# Controller_-_ESP32_Wroom_-_Rev_B.net
KiCad netlist of a schematic drawn in EAGLE
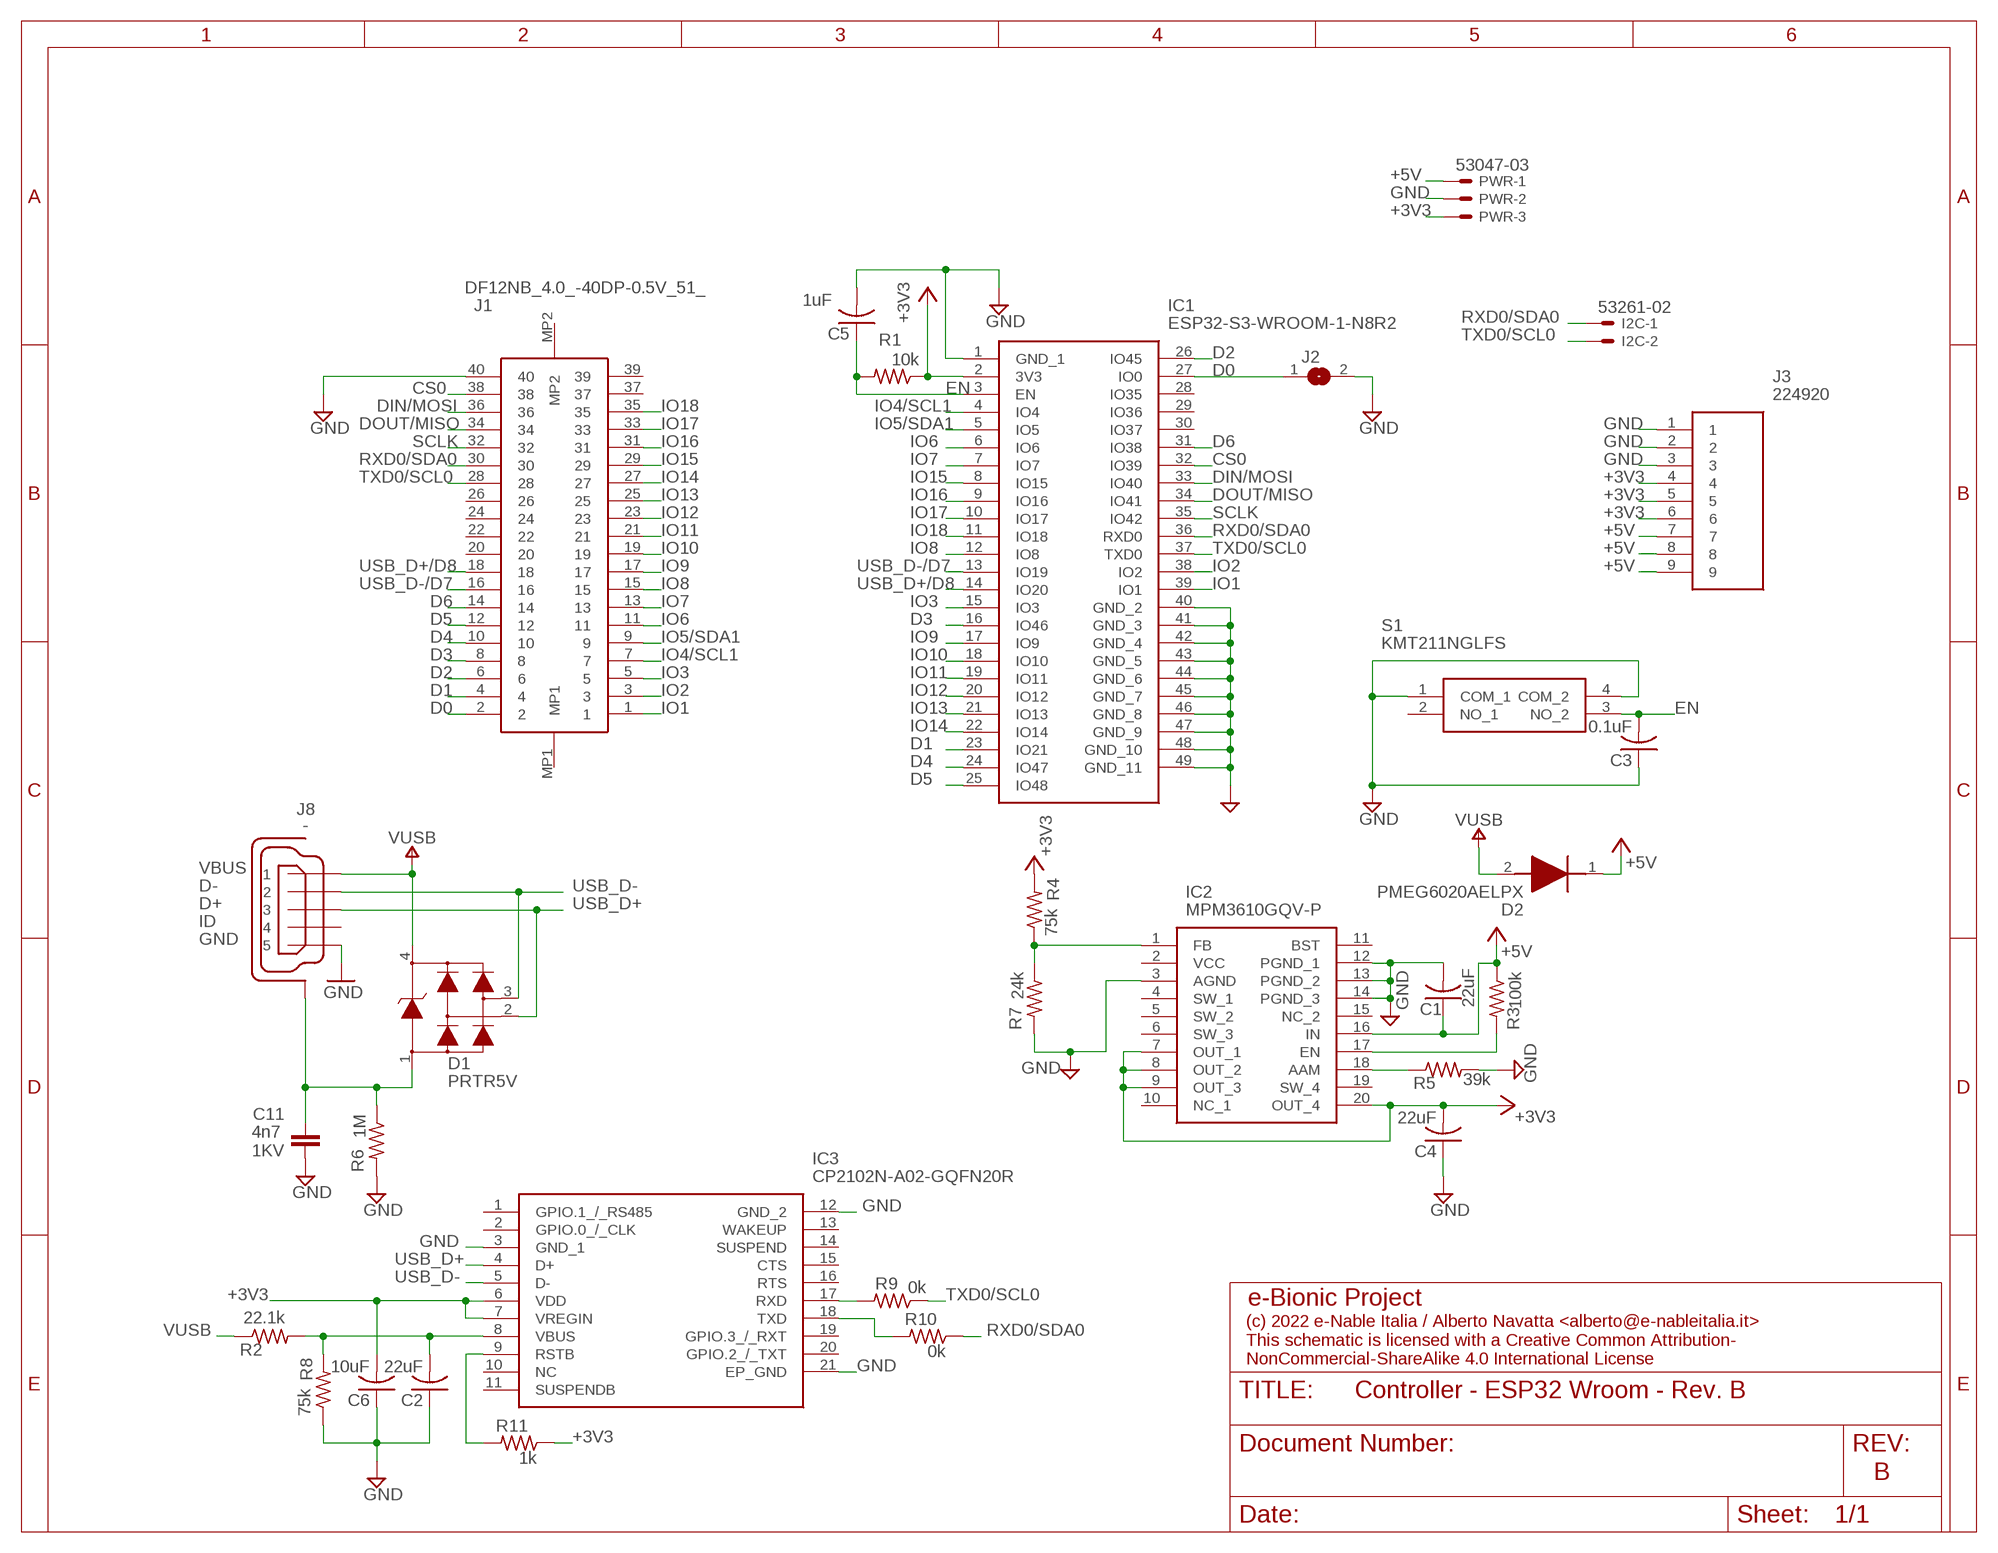
[diagram p0: schematic, sheet 1]

(export (version "E")
  (design (tool "Eeschema 10.0.6"))
  (components
    (comp (ref "C1")
      (value "22uF")
      (footprint "eagle-import:C0603")
      (libsource (lib "eagle-import") (part "C-USC0603"))
    )
    (comp (ref "C2")
      (value "22uF")
      (footprint "eagle-import:C0402")
      (libsource (lib "eagle-import") (part "C-USC0402"))
    )
    (comp (ref "C3")
      (value "0.1uF")
      (footprint "eagle-import:C0402")
      (libsource (lib "eagle-import") (part "C-USC0402"))
    )
    (comp (ref "C4")
      (value "22uF")
      (footprint "eagle-import:C0603")
      (libsource (lib "eagle-import") (part "C-USC0603"))
    )
    (comp (ref "C5")
      (value "1uF")
      (footprint "eagle-import:C0402")
      (libsource (lib "eagle-import") (part "C-USC0402"))
    )
    (comp (ref "C6")
      (value "10uF")
      (footprint "eagle-import:C0402")
      (libsource (lib "eagle-import") (part "C-USC0402"))
    )
    (comp (ref "C11")
      (value "4n7")
      (footprint "eagle-import:0805-R2013X50N")
      (fields (field (name "MANUFACTURER") "Kemet") (field (name "VOLTAGE") "1KV"))
      (libsource (lib "eagle-import") (part "C-08054.7NF"))
    )
    (comp (ref "D1")
      (value "PRTR5V")
      (footprint "eagle-import:SOT190P230X110-4N")
      (fields (field (name "MANUFACTURER") "NXP"))
      (libsource (lib "eagle-import") (part "PRTR5V0U2X,215"))
    )
    (comp (ref "D2")
      (value "PMEG6020AELPX")
      (footprint "eagle-import:SODFL4725X110N")
      (fields (field (name "MOUSER_PART_NUMBER") "771-PMEG6020AELPX"))
      (libsource (lib "eagle-import") (part "PMEG6020AELPX"))
    )
    (comp (ref "I2C")
      (value "53261-02")
      (footprint "eagle-import:53261-02")
      (fields (field (name "MF") "MOLEX"))
      (libsource (lib "eagle-import") (part "53?-02261"))
    )
    (comp (ref "IC1")
      (value "ESP32-S3-WROOM-1-N8R2")
      (footprint "eagle-import:ESP32S3WROOM1N8R2")
      (fields (field (name "MOUSER_PART_NUMBER") "356-ESP32-S3WRM1N8R2"))
      (libsource (lib "eagle-import") (part "ESP32-S3-WROOM-1-N8R2"))
    )
    (comp (ref "IC2")
      (value "MPM3610GQV-P")
      (footprint "eagle-import:MPM3610GQVP")
      (fields (field (name "MOUSER_PART_NUMBER") "946-MPM3610GQV-P"))
      (libsource (lib "eagle-import") (part "MPM3610GQV-P"))
    )
    (comp (ref "IC3")
      (value "CP2102N-A02-GQFN20R")
      (footprint "eagle-import:CP2102NA02GQFN20")
      (fields (field (name "MOUSER_PART_NUMBER") "634-CP2102NA02QFN20R"))
      (libsource (lib "eagle-import") (part "CP2102N-A02-GQFN20R"))
    )
    (comp (ref "J1")
      (value "DF12NB_4.0_-40DP-0.5V_51_")
      (footprint "eagle-import:DF12NB4040DP05V51")
      (fields
        (field (name "MANUFACTURER_PART_NUMBER") "DF12NB(4.0)-40DP-0.5V(51)")
        (field (name "MOUSER_PART_NUMBER") "798-DF12NB4040DP0551")
      )
      (libsource (lib "eagle-import") (part "DF12NB_4.0_-40DP-0.5V_51_"))
    )
    (comp (ref "J2") (value "SJ") (footprint "eagle-import:SJ") (libsource (lib "eagle-import") (part "SJ")))
    (comp (ref "J3")
      (value "224920")
      (footprint "eagle-import:224920")
      (fields (field (name "MOUSER_PART_NUMBER") "305-224920"))
      (libsource (lib "eagle-import") (part "224920"))
    )
    (comp (ref "J8")
      (value "-")
      (footprint "eagle-import:ZX62-AB-5PA")
      (fields (field (name "MANUFACTURER") "Hirose"))
      (libsource (lib "eagle-import") (part "USB-MICRO"))
    )
    (comp (ref "PWR")
      (value "53047-03")
      (footprint "eagle-import:53047-03")
      (fields (field (name "MF") "MOLEX") (field (name "MPN") "530470310"))
      (libsource (lib "eagle-import") (part "53?-03047"))
    )
    (comp (ref "R1")
      (value "10k")
      (footprint "eagle-import:R0402")
      (libsource (lib "eagle-import") (part "R-US_R0402"))
    )
    (comp (ref "R2")
      (value "22.1k")
      (footprint "eagle-import:R0402")
      (libsource (lib "eagle-import") (part "R-US_R0402"))
    )
    (comp (ref "R3")
      (value "100k")
      (footprint "eagle-import:R0402")
      (libsource (lib "eagle-import") (part "R-US_R0402"))
    )
    (comp (ref "R4")
      (value "75k")
      (footprint "eagle-import:R0402")
      (libsource (lib "eagle-import") (part "R-US_R0402"))
    )
    (comp (ref "R5")
      (value "39k")
      (footprint "eagle-import:R0402")
      (libsource (lib "eagle-import") (part "R-US_R0402"))
    )
    (comp (ref "R6")
      (value "1M")
      (footprint "eagle-import:R0402")
      (libsource (lib "eagle-import") (part "R-US_R0402"))
    )
    (comp (ref "R7")
      (value "24k")
      (footprint "eagle-import:R0402")
      (libsource (lib "eagle-import") (part "R-US_R0402"))
    )
    (comp (ref "R8")
      (value "75k")
      (footprint "eagle-import:R0402")
      (libsource (lib "eagle-import") (part "R-US_R0402"))
    )
    (comp (ref "R9")
      (value "0k")
      (footprint "eagle-import:R0402")
      (libsource (lib "eagle-import") (part "R-US_R0402"))
    )
    (comp (ref "R10")
      (value "0k")
      (footprint "eagle-import:R0402")
      (libsource (lib "eagle-import") (part "R-US_R0402"))
    )
    (comp (ref "R11")
      (value "1k")
      (footprint "eagle-import:R0402")
      (libsource (lib "eagle-import") (part "R-US_R0402"))
    )
    (comp (ref "S1")
      (value "KMT211NGLFS")
      (footprint "eagle-import:KMT211NGLFS")
      (fields (field (name "MOUSER_PART_NUMBER") "611-KMT211NGLFS"))
      (libsource (lib "eagle-import") (part "KMT211NGLFS"))
    )
  )
  (nets
    (net (code "1") (name "+3V3") (class "Default")
      (node (ref "C4") (pin "2") (pinfunction "2_2") (pintype "passive"))
      (node (ref "C6") (pin "2") (pinfunction "2_2") (pintype "passive"))
      (node (ref "IC1") (pin "2") (pinfunction "3V3_2") (pintype "bidirectional"))
      (node (ref "IC2") (pin "20") (pinfunction "OUT_4_20") (pintype "bidirectional"))
      (node (ref "IC2") (pin "7") (pinfunction "OUT_1_7") (pintype "bidirectional"))
      (node (ref "IC2") (pin "8") (pinfunction "OUT_2_8") (pintype "bidirectional"))
      (node (ref "IC2") (pin "9") (pinfunction "OUT_3_9") (pintype "bidirectional"))
      (node (ref "IC3") (pin "6") (pinfunction "VDD_6") (pintype "bidirectional"))
      (node (ref "IC3") (pin "7") (pinfunction "VREGIN_7") (pintype "bidirectional"))
      (node (ref "J3") (pin "4") (pinfunction "4_4") (pintype "bidirectional"))
      (node (ref "J3") (pin "5") (pinfunction "5_5") (pintype "bidirectional"))
      (node (ref "J3") (pin "6") (pinfunction "6_6") (pintype "bidirectional"))
      (node (ref "PWR") (pin "3") (pinfunction "S_3") (pintype "passive"))
      (node (ref "R1") (pin "1") (pinfunction "1_1") (pintype "passive"))
      (node (ref "R11") (pin "1") (pinfunction "1_1") (pintype "passive"))
      (node (ref "R4") (pin "2") (pinfunction "2_2") (pintype "passive"))
    )
    (net (code "2") (name "+5V") (class "Default")
      (node (ref "C1") (pin "1") (pinfunction "1_1") (pintype "passive"))
      (node (ref "D2") (pin "1") (pinfunction "K_1") (pintype "bidirectional"))
      (node (ref "IC2") (pin "16") (pinfunction "IN_16") (pintype "bidirectional"))
      (node (ref "J3") (pin "7") (pinfunction "7_7") (pintype "bidirectional"))
      (node (ref "J3") (pin "8") (pinfunction "8_8") (pintype "bidirectional"))
      (node (ref "J3") (pin "9") (pinfunction "9_9") (pintype "bidirectional"))
      (node (ref "PWR") (pin "1") (pinfunction "S_1") (pintype "passive"))
      (node (ref "R3") (pin "1") (pinfunction "1_1") (pintype "passive"))
    )
    (net (code "3") (name "/CS0") (class "Default")
      (node (ref "IC1") (pin "32") (pinfunction "IO39_32") (pintype "bidirectional"))
      (node (ref "J1") (pin "38") (pinfunction "38_38") (pintype "bidirectional"))
    )
    (net (code "4") (name "/D0") (class "Default")
      (node (ref "IC1") (pin "27") (pinfunction "IO0_27") (pintype "bidirectional"))
      (node (ref "J1") (pin "2") (pinfunction "2_2") (pintype "bidirectional"))
      (node (ref "J2") (pin "1") (pinfunction "1_1") (pintype "passive"))
    )
    (net (code "5") (name "/D1") (class "Default")
      (node (ref "IC1") (pin "23") (pinfunction "IO21_23") (pintype "bidirectional"))
      (node (ref "J1") (pin "4") (pinfunction "4_4") (pintype "bidirectional"))
    )
    (net (code "6") (name "/D2") (class "Default")
      (node (ref "IC1") (pin "26") (pinfunction "IO45_26") (pintype "bidirectional"))
      (node (ref "J1") (pin "6") (pinfunction "6_6") (pintype "bidirectional"))
    )
    (net (code "7") (name "/D3") (class "Default")
      (node (ref "IC1") (pin "16") (pinfunction "IO46_16") (pintype "bidirectional"))
      (node (ref "J1") (pin "8") (pinfunction "8_8") (pintype "bidirectional"))
    )
    (net (code "8") (name "/D4") (class "Default")
      (node (ref "IC1") (pin "24") (pinfunction "IO47_24") (pintype "bidirectional"))
      (node (ref "J1") (pin "10") (pinfunction "10_10") (pintype "bidirectional"))
    )
    (net (code "9") (name "/D5") (class "Default")
      (node (ref "IC1") (pin "25") (pinfunction "IO48_25") (pintype "bidirectional"))
      (node (ref "J1") (pin "12") (pinfunction "12_12") (pintype "bidirectional"))
    )
    (net (code "10") (name "/D6") (class "Default")
      (node (ref "IC1") (pin "31") (pinfunction "IO38_31") (pintype "bidirectional"))
      (node (ref "J1") (pin "14") (pinfunction "14_14") (pintype "bidirectional"))
    )
    (net (code "11") (name "/DIN{slash}MOSI") (class "Default")
      (node (ref "IC1") (pin "33") (pinfunction "IO40_33") (pintype "bidirectional"))
      (node (ref "J1") (pin "36") (pinfunction "36_36") (pintype "bidirectional"))
    )
    (net (code "12") (name "/DOUT{slash}MISO") (class "Default")
      (node (ref "IC1") (pin "34") (pinfunction "IO41_34") (pintype "bidirectional"))
      (node (ref "J1") (pin "34") (pinfunction "34_34") (pintype "bidirectional"))
    )
    (net (code "13") (name "/EN") (class "Default")
      (node (ref "C3") (pin "2") (pinfunction "2_2") (pintype "passive"))
      (node (ref "C5") (pin "1") (pinfunction "1_1") (pintype "passive"))
      (node (ref "IC1") (pin "3") (pinfunction "EN_3") (pintype "bidirectional"))
      (node (ref "R1") (pin "2") (pinfunction "2_2") (pintype "passive"))
      (node (ref "S1") (pin "3") (pinfunction "NO_2_3") (pintype "bidirectional"))
    )
    (net (code "14") (name "/IO1") (class "Default")
      (node (ref "IC1") (pin "39") (pinfunction "IO1_39") (pintype "bidirectional"))
      (node (ref "J1") (pin "1") (pinfunction "1_1") (pintype "bidirectional"))
    )
    (net (code "15") (name "/IO2") (class "Default")
      (node (ref "IC1") (pin "38") (pinfunction "IO2_38") (pintype "bidirectional"))
      (node (ref "J1") (pin "3") (pinfunction "3_3") (pintype "bidirectional"))
    )
    (net (code "16") (name "/IO3") (class "Default")
      (node (ref "IC1") (pin "15") (pinfunction "IO3_15") (pintype "bidirectional"))
      (node (ref "J1") (pin "5") (pinfunction "5_5") (pintype "bidirectional"))
    )
    (net (code "17") (name "/IO4{slash}SCL1") (class "Default")
      (node (ref "IC1") (pin "4") (pinfunction "IO4_4") (pintype "bidirectional"))
      (node (ref "J1") (pin "7") (pinfunction "7_7") (pintype "bidirectional"))
    )
    (net (code "18") (name "/IO5{slash}SDA1") (class "Default")
      (node (ref "IC1") (pin "5") (pinfunction "IO5_5") (pintype "bidirectional"))
      (node (ref "J1") (pin "9") (pinfunction "9_9") (pintype "bidirectional"))
    )
    (net (code "19") (name "/IO6") (class "Default")
      (node (ref "IC1") (pin "6") (pinfunction "IO6_6") (pintype "bidirectional"))
      (node (ref "J1") (pin "11") (pinfunction "11_11") (pintype "bidirectional"))
    )
    (net (code "20") (name "/IO7") (class "Default")
      (node (ref "IC1") (pin "7") (pinfunction "IO7_7") (pintype "bidirectional"))
      (node (ref "J1") (pin "13") (pinfunction "13_13") (pintype "bidirectional"))
    )
    (net (code "21") (name "/IO8") (class "Default")
      (node (ref "IC1") (pin "12") (pinfunction "IO8_12") (pintype "bidirectional"))
      (node (ref "J1") (pin "15") (pinfunction "15_15") (pintype "bidirectional"))
    )
    (net (code "22") (name "/IO9") (class "Default")
      (node (ref "IC1") (pin "17") (pinfunction "IO9_17") (pintype "bidirectional"))
      (node (ref "J1") (pin "17") (pinfunction "17_17") (pintype "bidirectional"))
    )
    (net (code "23") (name "/IO10") (class "Default")
      (node (ref "IC1") (pin "18") (pinfunction "IO10_18") (pintype "bidirectional"))
      (node (ref "J1") (pin "19") (pinfunction "19_19") (pintype "bidirectional"))
    )
    (net (code "24") (name "/IO11") (class "Default")
      (node (ref "IC1") (pin "19") (pinfunction "IO11_19") (pintype "bidirectional"))
      (node (ref "J1") (pin "21") (pinfunction "21_21") (pintype "bidirectional"))
    )
    (net (code "25") (name "/IO12") (class "Default")
      (node (ref "IC1") (pin "20") (pinfunction "IO12_20") (pintype "bidirectional"))
      (node (ref "J1") (pin "23") (pinfunction "23_23") (pintype "bidirectional"))
    )
    (net (code "26") (name "/IO13") (class "Default")
      (node (ref "IC1") (pin "21") (pinfunction "IO13_21") (pintype "bidirectional"))
      (node (ref "J1") (pin "25") (pinfunction "25_25") (pintype "bidirectional"))
    )
    (net (code "27") (name "/IO14") (class "Default")
      (node (ref "IC1") (pin "22") (pinfunction "IO14_22") (pintype "bidirectional"))
      (node (ref "J1") (pin "27") (pinfunction "27_27") (pintype "bidirectional"))
    )
    (net (code "28") (name "/IO15") (class "Default")
      (node (ref "IC1") (pin "8") (pinfunction "IO15_8") (pintype "bidirectional"))
      (node (ref "J1") (pin "29") (pinfunction "29_29") (pintype "bidirectional"))
    )
    (net (code "29") (name "/IO16") (class "Default")
      (node (ref "IC1") (pin "9") (pinfunction "IO16_9") (pintype "bidirectional"))
      (node (ref "J1") (pin "31") (pinfunction "31_31") (pintype "bidirectional"))
    )
    (net (code "30") (name "/IO17") (class "Default")
      (node (ref "IC1") (pin "10") (pinfunction "IO17_10") (pintype "bidirectional"))
      (node (ref "J1") (pin "33") (pinfunction "33_33") (pintype "bidirectional"))
    )
    (net (code "31") (name "/IO18") (class "Default")
      (node (ref "IC1") (pin "11") (pinfunction "IO18_11") (pintype "bidirectional"))
      (node (ref "J1") (pin "35") (pinfunction "35_35") (pintype "bidirectional"))
    )
    (net (code "32") (name "/RXD0{slash}SDA0") (class "Default")
      (node (ref "I2C") (pin "1") (pinfunction "S_1") (pintype "passive"))
      (node (ref "IC1") (pin "36") (pinfunction "RXD0_36") (pintype "bidirectional"))
      (node (ref "J1") (pin "30") (pinfunction "30_30") (pintype "bidirectional"))
      (node (ref "R10") (pin "1") (pinfunction "1_1") (pintype "passive"))
    )
    (net (code "33") (name "/SCLK") (class "Default")
      (node (ref "IC1") (pin "35") (pinfunction "IO42_35") (pintype "bidirectional"))
      (node (ref "J1") (pin "32") (pinfunction "32_32") (pintype "bidirectional"))
    )
    (net (code "34") (name "/TXD0{slash}SCL0") (class "Default")
      (node (ref "I2C") (pin "2") (pinfunction "S_2") (pintype "passive"))
      (node (ref "IC1") (pin "37") (pinfunction "TXD0_37") (pintype "bidirectional"))
      (node (ref "J1") (pin "28") (pinfunction "28_28") (pintype "bidirectional"))
      (node (ref "R9") (pin "1") (pinfunction "1_1") (pintype "passive"))
    )
    (net (code "35") (name "/USB_D+") (class "Default")
      (node (ref "D1") (pin "2") (pinfunction "2_2") (pintype "passive"))
      (node (ref "IC3") (pin "4") (pinfunction "D+_4") (pintype "bidirectional"))
      (node (ref "J8") (pin "3") (pinfunction "3_3") (pintype "passive"))
    )
    (net (code "36") (name "/USB_D+{slash}D8") (class "Default")
      (node (ref "IC1") (pin "14") (pinfunction "IO20_14") (pintype "bidirectional"))
      (node (ref "J1") (pin "18") (pinfunction "18_18") (pintype "bidirectional"))
    )
    (net (code "37") (name "/USB_D-") (class "Default")
      (node (ref "D1") (pin "3") (pinfunction "3_3") (pintype "passive"))
      (node (ref "IC3") (pin "5") (pinfunction "D-_5") (pintype "bidirectional"))
      (node (ref "J8") (pin "2") (pinfunction "2_2") (pintype "passive"))
    )
    (net (code "38") (name "/USB_D-{slash}D7") (class "Default")
      (node (ref "IC1") (pin "13") (pinfunction "IO19_13") (pintype "bidirectional"))
      (node (ref "J1") (pin "16") (pinfunction "16_16") (pintype "bidirectional"))
    )
    (net (code "39") (name "GND") (class "Default")
      (node (ref "C1") (pin "2") (pinfunction "2_2") (pintype "passive"))
      (node (ref "C11") (pin "2") (pinfunction "2_2") (pintype "passive"))
      (node (ref "C2") (pin "1") (pinfunction "1_1") (pintype "passive"))
      (node (ref "C3") (pin "1") (pinfunction "1_1") (pintype "passive"))
      (node (ref "C4") (pin "1") (pinfunction "1_1") (pintype "passive"))
      (node (ref "C5") (pin "2") (pinfunction "2_2") (pintype "passive"))
      (node (ref "C6") (pin "1") (pinfunction "1_1") (pintype "passive"))
      (node (ref "IC1") (pin "1") (pinfunction "GND_1_1") (pintype "bidirectional"))
      (node (ref "IC1") (pin "40") (pinfunction "GND_2_40") (pintype "bidirectional"))
      (node (ref "IC1") (pin "41") (pinfunction "GND_3_41") (pintype "bidirectional"))
      (node (ref "IC1") (pin "42") (pinfunction "GND_4_42") (pintype "bidirectional"))
      (node (ref "IC1") (pin "43") (pinfunction "GND_5_43") (pintype "bidirectional"))
      (node (ref "IC1") (pin "44") (pinfunction "GND_6_44") (pintype "bidirectional"))
      (node (ref "IC1") (pin "45") (pinfunction "GND_7_45") (pintype "bidirectional"))
      (node (ref "IC1") (pin "46") (pinfunction "GND_8_46") (pintype "bidirectional"))
      (node (ref "IC1") (pin "47") (pinfunction "GND_9_47") (pintype "bidirectional"))
      (node (ref "IC1") (pin "48") (pinfunction "GND_10_48") (pintype "bidirectional"))
      (node (ref "IC1") (pin "49") (pinfunction "GND_11_49") (pintype "bidirectional"))
      (node (ref "IC2") (pin "12") (pinfunction "PGND_1_12") (pintype "bidirectional"))
      (node (ref "IC2") (pin "13") (pinfunction "PGND_2_13") (pintype "bidirectional"))
      (node (ref "IC2") (pin "14") (pinfunction "PGND_3_14") (pintype "bidirectional"))
      (node (ref "IC2") (pin "3") (pinfunction "AGND_3") (pintype "bidirectional"))
      (node (ref "IC3") (pin "12") (pinfunction "GND_2_12") (pintype "bidirectional"))
      (node (ref "IC3") (pin "21") (pinfunction "EP_GND_21") (pintype "bidirectional"))
      (node (ref "IC3") (pin "3") (pinfunction "GND_1_3") (pintype "bidirectional"))
      (node (ref "J1") (pin "40") (pinfunction "40_40") (pintype "bidirectional"))
      (node (ref "J2") (pin "2") (pinfunction "2_2") (pintype "passive"))
      (node (ref "J3") (pin "1") (pinfunction "1_1") (pintype "bidirectional"))
      (node (ref "J3") (pin "2") (pinfunction "2_2") (pintype "bidirectional"))
      (node (ref "J3") (pin "3") (pinfunction "3_3") (pintype "bidirectional"))
      (node (ref "J8") (pin "5") (pinfunction "5_5") (pintype "passive"))
      (node (ref "PWR") (pin "2") (pinfunction "S_2") (pintype "passive"))
      (node (ref "R5") (pin "2") (pinfunction "2_2") (pintype "passive"))
      (node (ref "R6") (pin "2") (pinfunction "2_2") (pintype "passive"))
      (node (ref "R7") (pin "2") (pinfunction "2_2") (pintype "passive"))
      (node (ref "R8") (pin "1") (pinfunction "1_1") (pintype "passive"))
      (node (ref "S1") (pin "1") (pinfunction "COM_1_1") (pintype "bidirectional"))
      (node (ref "S1") (pin "4") (pinfunction "COM_2_4") (pintype "bidirectional"))
    )
    (net (code "40") (name "Net-(C11-Pad1)") (class "Default")
      (node (ref "C11") (pin "1") (pinfunction "1_1") (pintype "passive"))
      (node (ref "D1") (pin "1") (pinfunction "1_1") (pintype "passive"))
      (node (ref "J8") (pin "10") (pinfunction "SH_10") (pintype "passive"))
      (node (ref "J8") (pin "11") (pinfunction "SH_11") (pintype "passive"))
      (node (ref "J8") (pin "6") (pinfunction "SH_6") (pintype "passive"))
      (node (ref "J8") (pin "7") (pinfunction "SH_7") (pintype "passive"))
      (node (ref "J8") (pin "8") (pinfunction "SH_8") (pintype "passive"))
      (node (ref "J8") (pin "9") (pinfunction "SH_9") (pintype "passive"))
      (node (ref "R6") (pin "1") (pinfunction "1_1") (pintype "passive"))
    )
    (net (code "41") (name "Net-(IC2-AAM)") (class "Default")
      (node (ref "IC2") (pin "18") (pinfunction "AAM_18") (pintype "bidirectional"))
      (node (ref "R5") (pin "1") (pinfunction "1_1") (pintype "passive"))
    )
    (net (code "42") (name "Net-(IC2-EN)") (class "Default")
      (node (ref "IC2") (pin "17") (pinfunction "EN_17") (pintype "bidirectional"))
      (node (ref "R3") (pin "2") (pinfunction "2_2") (pintype "passive"))
    )
    (net (code "43") (name "Net-(IC2-FB)") (class "Default")
      (node (ref "IC2") (pin "1") (pinfunction "FB_1") (pintype "bidirectional"))
      (node (ref "R4") (pin "1") (pinfunction "1_1") (pintype "passive"))
      (node (ref "R7") (pin "1") (pinfunction "1_1") (pintype "passive"))
    )
    (net (code "44") (name "Net-(IC3-RSTB)") (class "Default")
      (node (ref "IC3") (pin "9") (pinfunction "RSTB_9") (pintype "bidirectional"))
      (node (ref "R11") (pin "2") (pinfunction "2_2") (pintype "passive"))
    )
    (net (code "45") (name "Net-(IC3-RXD)") (class "Default")
      (node (ref "IC3") (pin "17") (pinfunction "RXD_17") (pintype "bidirectional"))
      (node (ref "R9") (pin "2") (pinfunction "2_2") (pintype "passive"))
    )
    (net (code "46") (name "Net-(IC3-TXD)") (class "Default")
      (node (ref "IC3") (pin "18") (pinfunction "TXD_18") (pintype "bidirectional"))
      (node (ref "R10") (pin "2") (pinfunction "2_2") (pintype "passive"))
    )
    (net (code "47") (name "Net-(IC3-VBUS)") (class "Default")
      (node (ref "C2") (pin "2") (pinfunction "2_2") (pintype "passive"))
      (node (ref "IC3") (pin "8") (pinfunction "VBUS_8") (pintype "bidirectional"))
      (node (ref "R2") (pin "2") (pinfunction "2_2") (pintype "passive"))
      (node (ref "R8") (pin "2") (pinfunction "2_2") (pintype "passive"))
    )
    (net (code "48") (name "VUSB") (class "Default")
      (node (ref "D1") (pin "4") (pinfunction "4_4") (pintype "passive"))
      (node (ref "D2") (pin "2") (pinfunction "A_2") (pintype "bidirectional"))
      (node (ref "J8") (pin "1") (pinfunction "1_1") (pintype "passive"))
      (node (ref "R2") (pin "1") (pinfunction "1_1") (pintype "passive"))
    )
    (net (code "49") (name "unconnected-(IC1-IO35-Pad28)") (class "Default")
      (node (ref "IC1") (pin "28") (pinfunction "IO35_28") (pintype "bidirectional"))
    )
    (net (code "50") (name "unconnected-(IC1-IO36-Pad29)") (class "Default")
      (node (ref "IC1") (pin "29") (pinfunction "IO36_29") (pintype "bidirectional"))
    )
    (net (code "51") (name "unconnected-(IC1-IO37-Pad30)") (class "Default")
      (node (ref "IC1") (pin "30") (pinfunction "IO37_30") (pintype "bidirectional"))
    )
    (net (code "52") (name "unconnected-(IC2-BST-Pad11)") (class "Default")
      (node (ref "IC2") (pin "11") (pinfunction "BST_11") (pintype "bidirectional"))
    )
    (net (code "53") (name "unconnected-(IC2-NC_1-Pad10)") (class "Default")
      (node (ref "IC2") (pin "10") (pinfunction "NC_1_10") (pintype "bidirectional"))
    )
    (net (code "54") (name "unconnected-(IC2-NC_2-Pad15)") (class "Default")
      (node (ref "IC2") (pin "15") (pinfunction "NC_2_15") (pintype "bidirectional"))
    )
    (net (code "55") (name "unconnected-(IC2-SW_1-Pad4)") (class "Default")
      (node (ref "IC2") (pin "4") (pinfunction "SW_1_4") (pintype "bidirectional"))
    )
    (net (code "56") (name "unconnected-(IC2-SW_2-Pad5)") (class "Default")
      (node (ref "IC2") (pin "5") (pinfunction "SW_2_5") (pintype "bidirectional"))
    )
    (net (code "57") (name "unconnected-(IC2-SW_3-Pad6)") (class "Default")
      (node (ref "IC2") (pin "6") (pinfunction "SW_3_6") (pintype "bidirectional"))
    )
    (net (code "58") (name "unconnected-(IC2-SW_4-Pad19)") (class "Default")
      (node (ref "IC2") (pin "19") (pinfunction "SW_4_19") (pintype "bidirectional"))
    )
    (net (code "59") (name "unconnected-(IC2-VCC-Pad2)") (class "Default")
      (node (ref "IC2") (pin "2") (pinfunction "VCC_2") (pintype "bidirectional"))
    )
    (net (code "60") (name "unconnected-(IC3-CTS-Pad15)") (class "Default")
      (node (ref "IC3") (pin "15") (pinfunction "CTS_15") (pintype "bidirectional"))
    )
    (net (code "61") (name "unconnected-(IC3-GPIO.0_{slash}_CLK-Pad2)") (class "Default")
      (node (ref "IC3") (pin "2") (pinfunction "GPIO.0_/_CLK_2") (pintype "bidirectional"))
    )
    (net (code "62") (name "unconnected-(IC3-GPIO.1_{slash}_RS485-Pad1)") (class "Default")
      (node (ref "IC3") (pin "1") (pinfunction "GPIO.1_/_RS485_1") (pintype "bidirectional"))
    )
    (net (code "63") (name "unconnected-(IC3-GPIO.2_{slash}_TXT-Pad20)") (class "Default")
      (node (ref "IC3") (pin "20") (pinfunction "GPIO.2_/_TXT_20") (pintype "bidirectional"))
    )
    (net (code "64") (name "unconnected-(IC3-GPIO.3_{slash}_RXT-Pad19)") (class "Default")
      (node (ref "IC3") (pin "19") (pinfunction "GPIO.3_/_RXT_19") (pintype "bidirectional"))
    )
    (net (code "65") (name "unconnected-(IC3-NC-Pad10)") (class "Default")
      (node (ref "IC3") (pin "10") (pinfunction "NC_10") (pintype "no_connect"))
    )
    (net (code "66") (name "unconnected-(IC3-RTS-Pad16)") (class "Default")
      (node (ref "IC3") (pin "16") (pinfunction "RTS_16") (pintype "bidirectional"))
    )
    (net (code "67") (name "unconnected-(IC3-SUSPEND-Pad14)") (class "Default")
      (node (ref "IC3") (pin "14") (pinfunction "SUSPEND_14") (pintype "bidirectional"))
    )
    (net (code "68") (name "unconnected-(IC3-SUSPENDB-Pad11)") (class "Default")
      (node (ref "IC3") (pin "11") (pinfunction "SUSPENDB_11") (pintype "bidirectional"))
    )
    (net (code "69") (name "unconnected-(IC3-WAKEUP-Pad13)") (class "Default")
      (node (ref "IC3") (pin "13") (pinfunction "WAKEUP_13") (pintype "bidirectional"))
    )
    (net (code "70") (name "unconnected-(J1-Pad20)") (class "Default")
      (node (ref "J1") (pin "20") (pinfunction "20_20") (pintype "bidirectional"))
    )
    (net (code "71") (name "unconnected-(J1-Pad22)") (class "Default")
      (node (ref "J1") (pin "22") (pinfunction "22_22") (pintype "bidirectional"))
    )
    (net (code "72") (name "unconnected-(J1-Pad24)") (class "Default")
      (node (ref "J1") (pin "24") (pinfunction "24_24") (pintype "bidirectional"))
    )
    (net (code "73") (name "unconnected-(J1-Pad26)") (class "Default")
      (node (ref "J1") (pin "26") (pinfunction "26_26") (pintype "bidirectional"))
    )
    (net (code "74") (name "unconnected-(J1-Pad37)") (class "Default")
      (node (ref "J1") (pin "37") (pinfunction "37_37") (pintype "bidirectional"))
    )
    (net (code "75") (name "unconnected-(J1-Pad39)") (class "Default")
      (node (ref "J1") (pin "39") (pinfunction "39_39") (pintype "bidirectional"))
    )
    (net (code "76") (name "unconnected-(J1-PadMP1)") (class "Default")
      (node (ref "J1") (pin "MP1") (pinfunction "MP1_MP1") (pintype "bidirectional"))
    )
    (net (code "77") (name "unconnected-(J1-PadMP2)") (class "Default")
      (node (ref "J1") (pin "MP2") (pinfunction "MP2_MP2") (pintype "bidirectional"))
    )
    (net (code "78") (name "unconnected-(J8-Pad4)") (class "Default")
      (node (ref "J8") (pin "4") (pinfunction "4_4") (pintype "passive"))
    )
    (net (code "79") (name "unconnected-(S1-NO_1-Pad2)") (class "Default")
      (node (ref "S1") (pin "2") (pinfunction "NO_1_2") (pintype "bidirectional"))
    )
  )
)
